# SHDN-IMD-S06-V00-PSU.net
KiCad netlist of a schematic drawn in Altium Designer
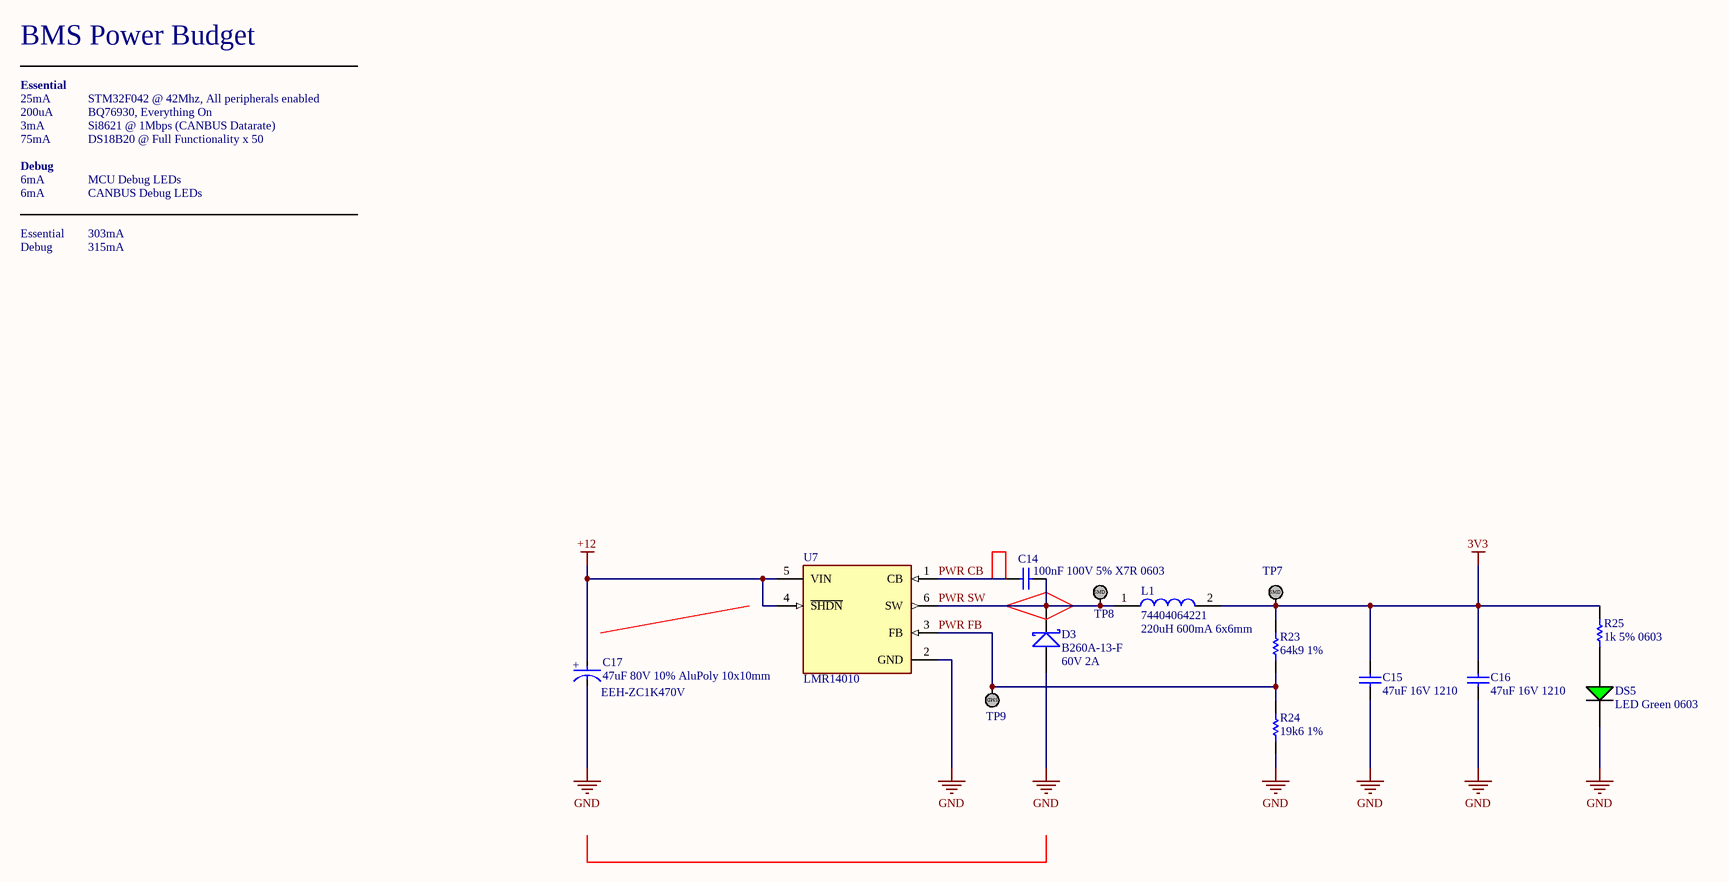
[diagram p0: SHDN-IMD-S06-V00-PSU.SchDoc]

(export (version "E")
  (design (tool "Eeschema 10.0.6"))
  (components
    (comp (ref "C14")
      (value "100nF 100V 5% X7R 0603")
      (footprint "Cap_Ceramic_0603")
      (description "Capacitor, Ceramic, SMD, 100nF, 100V, 5%, X7R, 0603")
      (libsource (lib "StandardCapacitors") (part "100nF 100V 5% X7R 0603"))
    )
    (comp (ref "C15")
      (value "47uF 16V 1210")
      (footprint "Cap_Ceramic_0603")
      (description "Capacitor, Ceramic, SMD, 47uF, 16V, 5%, X7R, 1210")
      (libsource (lib "StandardCapacitors") (part "47uF 16V 10% X7R 1210"))
    )
    (comp (ref "C16")
      (value "47uF 16V 1210")
      (footprint "Cap_Ceramic_0603")
      (description "Capacitor, Ceramic, SMD, 47uF, 16V, 5%, X7R, 1210")
      (libsource (lib "StandardCapacitors") (part "47uF 16V 10% X7R 1210"))
    )
    (comp (ref "C17")
      (value "47uF 80V 10% AluPoly 10x10mm")
      (footprint "CAP_ALU_10x10mm")
      (description "Capacitor, AluPoly, SMD, 47uF, 80V, 10%, AluPoly, 10x10mm")
      (libsource (lib "StandardCapacitors") (part "47uF 80V 10% AluPoly 10x10mm"))
    )
    (comp (ref "D3")
      (value "B260A-13-F")
      (footprint "SMA")
      (description "Diode, Schottky Barrier Rectifier, 60 V, 2 A, B260A-13-F")
      (libsource (lib "QUTMS_DiodeLibrary") (part "B260A-13-F"))
    )
    (comp (ref "DS5")
      (value "LED Green 0603")
      (footprint "LED GREEN 0603")
      (libsource (lib "QUTMS_LEDLibrary") (part "LED Green 0603"))
    )
    (comp (ref "L1")
      (value "74404064221")
      (footprint "Inductor_6x6mm")
      (description "FIXED IND 220UH 660MA 850 MOHM")
      (libsource (lib "QUTMS_InductorLibrary") (part "74404064221"))
    )
    (comp (ref "R23")
      (value "64k9 1%")
      (footprint "Res_ThinFilm_0603")
      (description "Resistor, SMD, 64k9, 0.1W, 5%, 0603")
      (libsource (lib "StandardResistors") (part "64k9 1% 0603"))
    )
    (comp (ref "R24")
      (value "19k6 1%")
      (footprint "Res_ThinFilm_0603")
      (description "Resistor, SMD, 19k6, 0.1W, 5%, 0603")
      (libsource (lib "StandardResistors") (part "19k6 1% 0603"))
    )
    (comp (ref "R25")
      (value "1k 5% 0603")
      (footprint "Res_ThinFilm_0603")
      (description "Resistor, SMD, 1k, 0.1W, 5%, 0603")
      (libsource (lib "StandardResistors") (part "1k 5% 0603"))
    )
    (comp (ref "TP7")
      (value "TestPoint_SMD")
      (footprint "TestPointSMD")
      (libsource (lib "StandardTest") (part "TestPoint_SMD"))
    )
    (comp (ref "TP8")
      (value "TestPoint_SMD")
      (footprint "TestPointSMD")
      (libsource (lib "StandardTest") (part "TestPoint_SMD"))
    )
    (comp (ref "TP9")
      (value "TestPoint_SMD")
      (footprint "TestPointSMD")
      (libsource (lib "StandardTest") (part "TestPoint_SMD"))
    )
    (comp (ref "U7")
      (value "LMR14010")
      (footprint "LMR14010")
      (libsource (lib "QUTMS_PowerSupplyLibrary") (part "LMR14010"))
    )
  )
  (nets
    (net (code "1") (name "+12") (class "Default")
      (node (ref "C17") (pin "A") (pinfunction "A_A") (pintype "passive"))
      (node (ref "U7") (pin "4") (pinfunction "~{SHDN}_4") (pintype "input"))
      (node (ref "U7") (pin "5") (pinfunction "VIN_5") (pintype "power_in"))
    )
    (net (code "2") (name "/PWR CB") (class "Default")
      (node (ref "C14") (pin "1") (pinfunction "1_1") (pintype "passive"))
      (node (ref "U7") (pin "1") (pinfunction "CB_1") (pintype "input"))
    )
    (net (code "3") (name "/PWR FB") (class "Default")
      (node (ref "R23") (pin "1") (pinfunction "1_1") (pintype "passive"))
      (node (ref "R24") (pin "2") (pinfunction "2_2") (pintype "passive"))
      (node (ref "TP9") (pin "1") (pinfunction "1_1") (pintype "passive"))
      (node (ref "U7") (pin "3") (pinfunction "FB_3") (pintype "input"))
    )
    (net (code "4") (name "/PWR SW") (class "Default")
      (node (ref "C14") (pin "2") (pinfunction "2_2") (pintype "passive"))
      (node (ref "D3") (pin "K") (pinfunction "K_K") (pintype "passive"))
      (node (ref "L1") (pin "1") (pinfunction "1_1") (pintype "passive"))
      (node (ref "TP8") (pin "1") (pinfunction "1_1") (pintype "passive"))
      (node (ref "U7") (pin "6") (pinfunction "SW_6") (pintype "output"))
    )
    (net (code "5") (name "3V3") (class "Default")
      (node (ref "C15") (pin "2") (pinfunction "2_2") (pintype "passive"))
      (node (ref "C16") (pin "2") (pinfunction "2_2") (pintype "passive"))
      (node (ref "L1") (pin "2") (pinfunction "2_2") (pintype "passive"))
      (node (ref "R23") (pin "2") (pinfunction "2_2") (pintype "passive"))
      (node (ref "R25") (pin "2") (pinfunction "2_2") (pintype "passive"))
      (node (ref "TP7") (pin "1") (pinfunction "1_1") (pintype "passive"))
    )
    (net (code "6") (name "GND") (class "Default")
      (node (ref "C15") (pin "1") (pinfunction "1_1") (pintype "passive"))
      (node (ref "C16") (pin "1") (pinfunction "1_1") (pintype "passive"))
      (node (ref "C17") (pin "K") (pinfunction "K_K") (pintype "passive"))
      (node (ref "D3") (pin "A") (pinfunction "A_A") (pintype "passive"))
      (node (ref "DS5") (pin "2") (pinfunction "C_2") (pintype "passive"))
      (node (ref "R24") (pin "1") (pinfunction "1_1") (pintype "passive"))
      (node (ref "U7") (pin "2") (pinfunction "GND_2") (pintype "power_in"))
    )
    (net (code "7") (name "Net-(DS5-A)") (class "Default")
      (node (ref "DS5") (pin "1") (pinfunction "A_1") (pintype "passive"))
      (node (ref "R25") (pin "1") (pinfunction "1_1") (pintype "passive"))
    )
  )
)
